# DM1095_Connector.net
KiCad netlist of a schematic drawn in Altium Designer
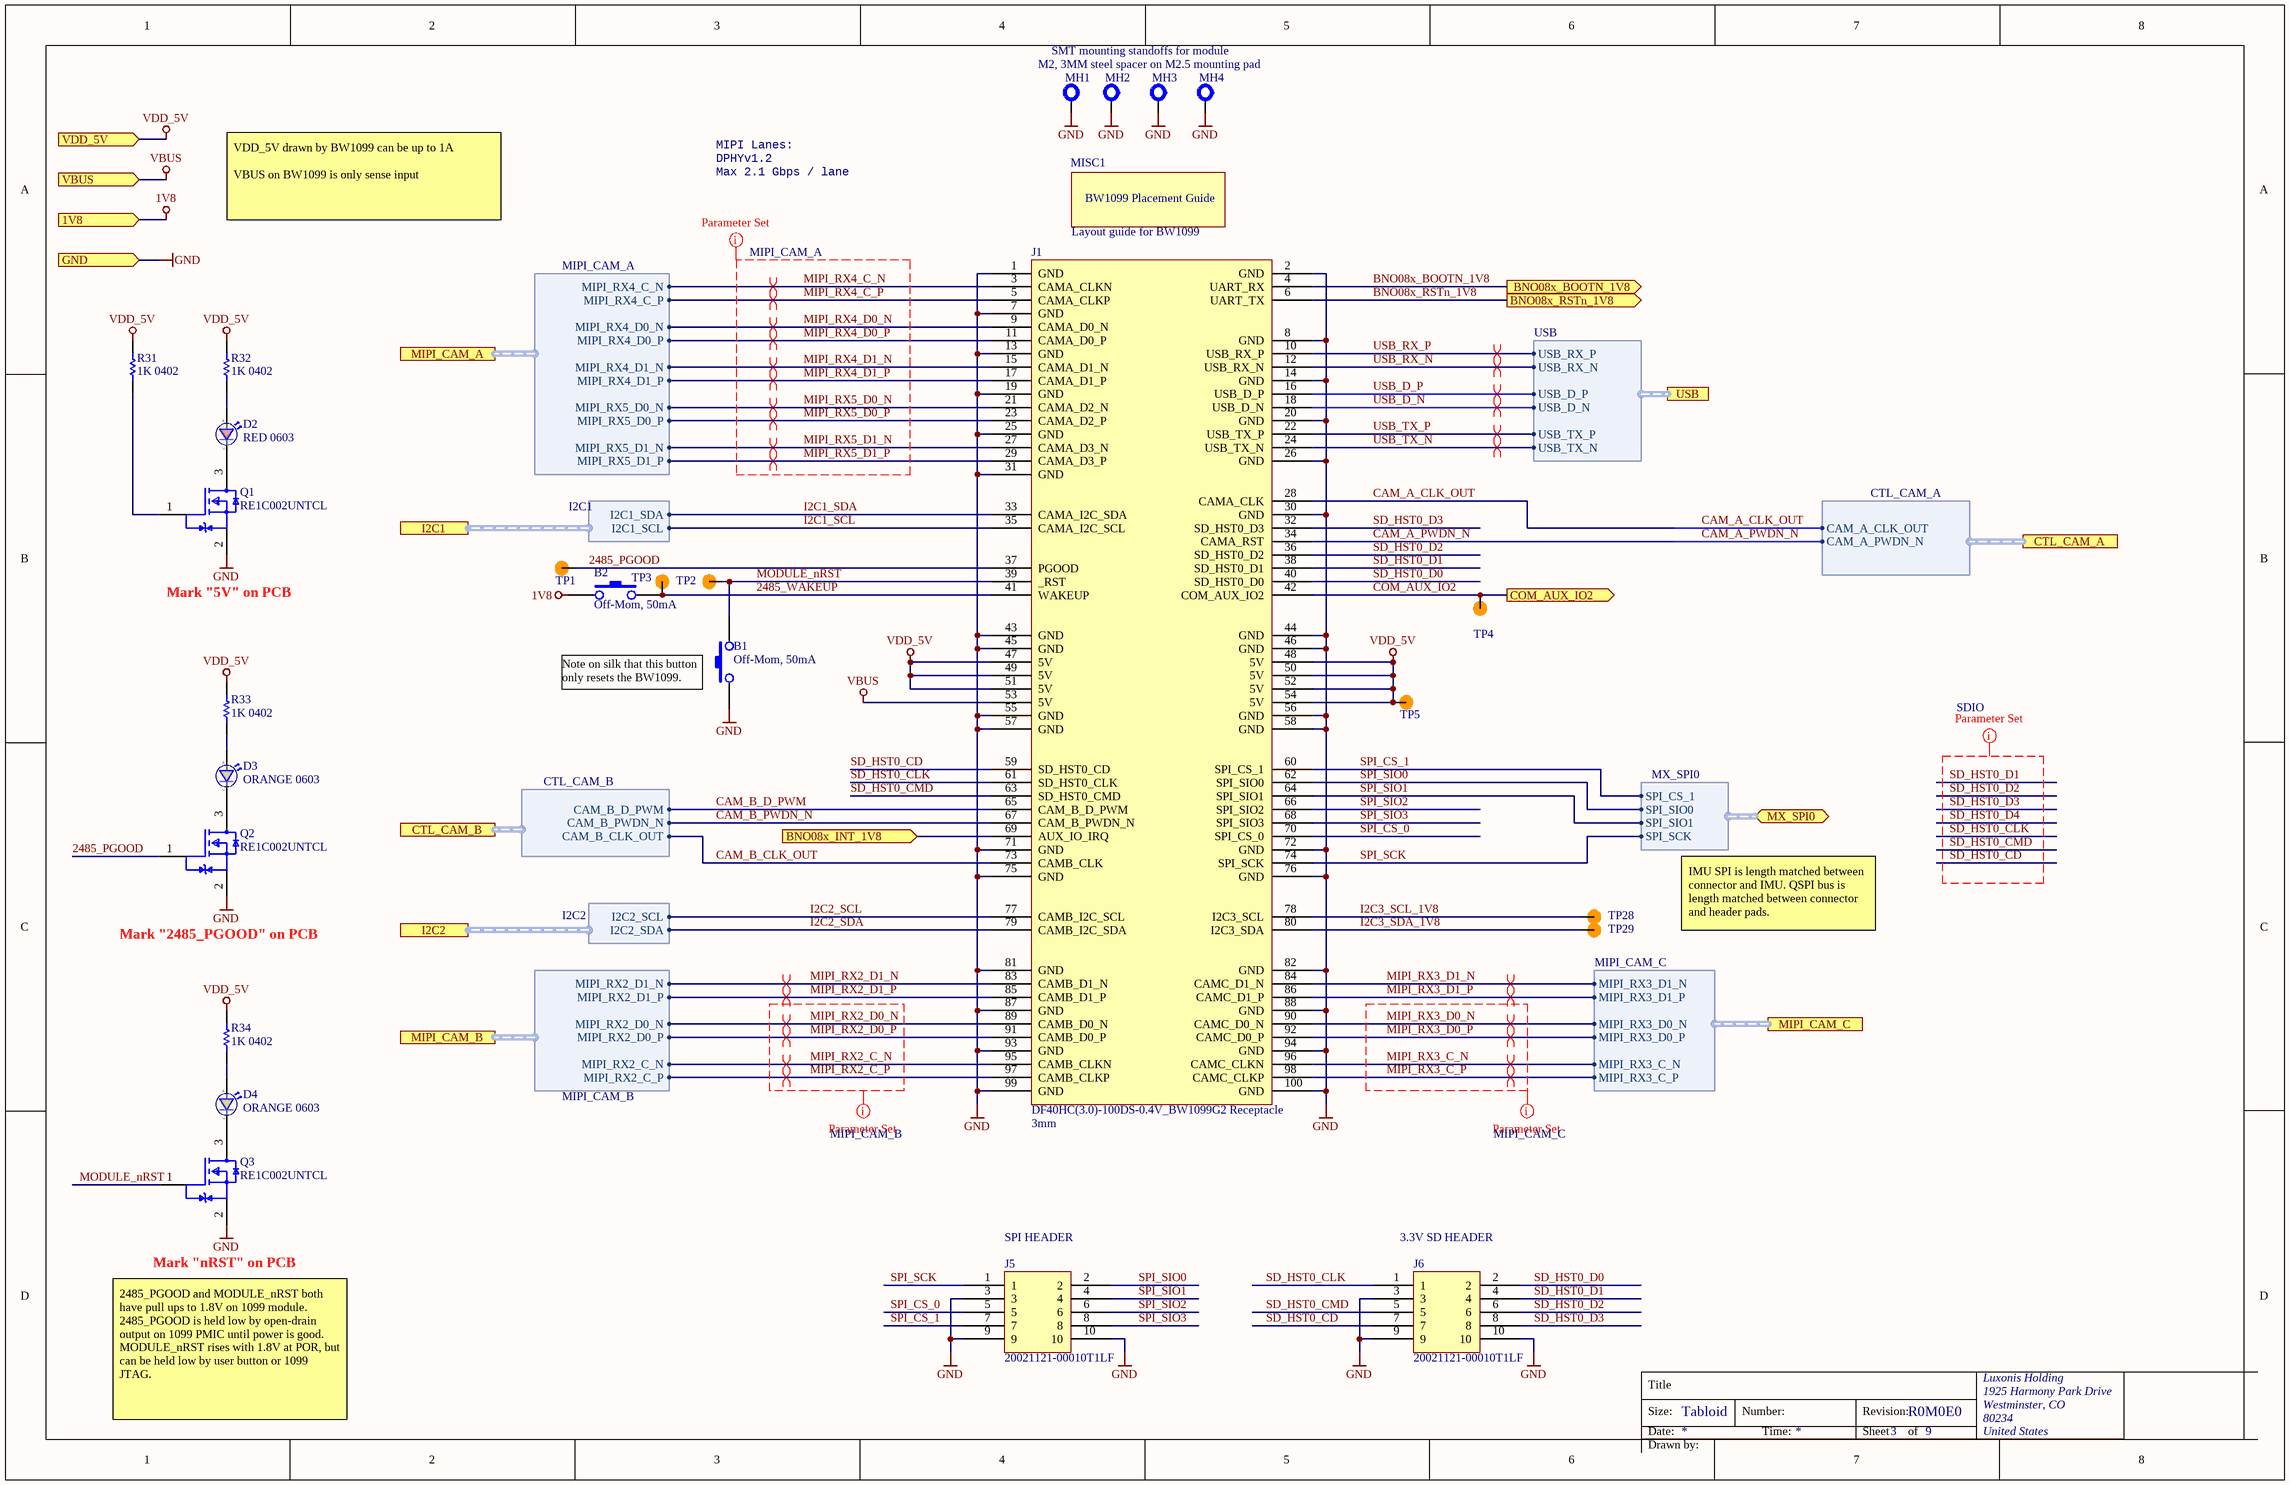
[diagram p0: DM1095_Connector.SchDoc]

(export (version "E")
  (design (tool "Eeschema 10.0.6"))
  (components
    (comp (ref "B1")
      (value "Off-Mom, 50mA")
      (footprint "LuxonisMaster:DTSM-32N-V")
      (description "SWITCH TACTILE SMT 3.5mm * 6mm , brown 160gf")
      (libsource (lib "LuxonisMaster") (part "DTSM-32N-V"))
    )
    (comp (ref "B2")
      (value "Off-Mom, 50mA")
      (footprint "LuxonisMaster:DTSM-32N-V")
      (description "SWITCH TACTILE SMT 3.5mm * 6mm , brown 160gf")
      (libsource (lib "LuxonisMaster") (part "DTSM-32N-V"))
    )
    (comp (ref "D2")
      (value "RED 0603")
      (footprint "LuxonisMaster:SML_D1xx8W")
      (description "LED RED DIFFUSED 0603 SMD Red 620nm LED Indication - Discrete 2.2V 0603 (1608 Metric)")
      (libsource (lib "LuxonisMaster") (part "SML-D12U8WT86"))
    )
    (comp (ref "D3")
      (value "ORANGE 0603")
      (footprint "LuxonisMaster:SML_D1xx8W")
      (description "LED ORANGE DIFFUSED 0603 SMD Orange 605nm LED Indication - Discrete 2.2V 0603 (1608 Metric)")
      (libsource (lib "LuxonisMaster") (part "SML-D12D8WT86"))
    )
    (comp (ref "D4")
      (value "ORANGE 0603")
      (footprint "LuxonisMaster:SML_D1xx8W")
      (description "LED ORANGE DIFFUSED 0603 SMD Orange 605nm LED Indication - Discrete 2.2V 0603 (1608 Metric)")
      (libsource (lib "LuxonisMaster") (part "SML-D12D8WT86"))
    )
    (comp (ref "J1")
      (value "DF40HC(3.0)-100DS-0.4V_BW1099G2 Receptacle")
      (footprint "LuxonisMaster:DF40HC-3.0-100DS-0.4V_minpad")
      (description "CONN RCPT 100POS 0.4MM SMD GOLD")
      (fields (field (name "MATED STACKING HEIGHT") "3mm"))
      (libsource (lib "LuxonisMaster") (part "DF40HC(3.0)-100DS-0.4V_BW1099_G2"))
    )
    (comp (ref "J5")
      (value "20021121-00010T1LF")
      (footprint "LuxonisMaster:20021121-00010T1LF")
      (description "CONN HEADER SMD 10POS 1.27MM")
      (libsource (lib "LuxonisMaster") (part "20021121-00010T1LF"))
    )
    (comp (ref "J6")
      (value "20021121-00010T1LF")
      (footprint "LuxonisMaster:20021121-00010T1LF")
      (description "CONN HEADER SMD 10POS 1.27MM")
      (libsource (lib "LuxonisMaster") (part "20021121-00010T1LF"))
    )
    (comp (ref "MH1")
      (value "M2, 3MM steel spacer on M2.5 mounting pad")
      (footprint "LuxonisMaster:9774030243R")
      (description "MP ROUND STANDOFF M2X0.4 STEEL 3MM")
      (libsource (lib "LuxonisMaster") (part "9774030243R"))
    )
    (comp (ref "MH2")
      (value "M2, 3MM steel spacer on M2.5 mounting pad")
      (footprint "LuxonisMaster:9774030243R")
      (description "MP ROUND STANDOFF M2X0.4 STEEL 3MM")
      (libsource (lib "LuxonisMaster") (part "9774030243R"))
    )
    (comp (ref "MH3")
      (value "M2, 3MM steel spacer on M2.5 mounting pad")
      (footprint "LuxonisMaster:9774030243R")
      (description "MP ROUND STANDOFF M2X0.4 STEEL 3MM")
      (libsource (lib "LuxonisMaster") (part "9774030243R"))
    )
    (comp (ref "MH4")
      (value "M2, 3MM steel spacer on M2.5 mounting pad")
      (footprint "LuxonisMaster:9774030243R")
      (description "MP ROUND STANDOFF M2X0.4 STEEL 3MM")
      (libsource (lib "LuxonisMaster") (part "9774030243R"))
    )
    (comp (ref "MISC1")
      (value "Layout guide for BW1099")
      (footprint "BW1099_R3_KTHSNF_Footprint")
      (description "MISC - Use for aligning BW1099 mount")
      (libsource (lib "LuxonisMaster") (part "BW1099_Footprint"))
    )
    (comp (ref "Q1")
      (value "RE1C002UNTCL")
      (footprint "LuxonisMaster:RE1C002UNTCL")
      (description "VISHAY - SI1062X-T1-GE3 - MOSFET Transistor, N Channel, 530 mA, 20 V, 0.35 ohm, 4.5 V, 1 V")
      (libsource (lib "LuxonisMaster") (part "RE1C002UNTCL"))
    )
    (comp (ref "Q2")
      (value "RE1C002UNTCL")
      (footprint "LuxonisMaster:RE1C002UNTCL")
      (description "VISHAY - SI1062X-T1-GE3 - MOSFET Transistor, N Channel, 530 mA, 20 V, 0.35 ohm, 4.5 V, 1 V")
      (libsource (lib "LuxonisMaster") (part "RE1C002UNTCL"))
    )
    (comp (ref "Q3")
      (value "RE1C002UNTCL")
      (footprint "LuxonisMaster:RE1C002UNTCL")
      (description "VISHAY - SI1062X-T1-GE3 - MOSFET Transistor, N Channel, 530 mA, 20 V, 0.35 ohm, 4.5 V, 1 V")
      (libsource (lib "LuxonisMaster") (part "RE1C002UNTCL"))
    )
    (comp (ref "R31")
      (value "1K 0402")
      (footprint "RES_Altium_Vault_Generic:RESC0402(1005)_L")
      (fields (field (name "TOLERANCE") "1%"))
      (libsource (lib "LuxonisMaster") (part "RC0402FR-071KL"))
    )
    (comp (ref "R32")
      (value "1K 0402")
      (footprint "RES_Altium_Vault_Generic:RESC0402(1005)_L")
      (fields (field (name "TOLERANCE") "1%"))
      (libsource (lib "LuxonisMaster") (part "RC0402FR-071KL"))
    )
    (comp (ref "R33")
      (value "1K 0402")
      (footprint "RES_Altium_Vault_Generic:RESC0402(1005)_L")
      (fields (field (name "TOLERANCE") "1%"))
      (libsource (lib "LuxonisMaster") (part "RC0402FR-071KL"))
    )
    (comp (ref "R34")
      (value "1K 0402")
      (footprint "RES_Altium_Vault_Generic:RESC0402(1005)_L")
      (fields (field (name "TOLERANCE") "1%"))
      (libsource (lib "LuxonisMaster") (part "RC0402FR-071KL"))
    )
    (comp (ref "TP1")
      (value "TP100_200_NS")
      (footprint "LuxonisMaster:TP100_200_NS")
      (libsource (lib "LuxonisMaster") (part "TEST_POINT"))
    )
    (comp (ref "TP2")
      (value "TP100_200_NS")
      (footprint "LuxonisMaster:TP100_200_NS")
      (libsource (lib "LuxonisMaster") (part "TEST_POINT"))
    )
    (comp (ref "TP3")
      (value "TP100_200_NS")
      (footprint "LuxonisMaster:TP100_200_NS")
      (libsource (lib "LuxonisMaster") (part "TEST_POINT"))
    )
    (comp (ref "TP4")
      (value "TP100_200_NS")
      (footprint "LuxonisMaster:TP100_200_NS")
      (libsource (lib "LuxonisMaster") (part "TEST_POINT"))
    )
    (comp (ref "TP5")
      (value "TP100_200_NS")
      (footprint "LuxonisMaster:TP100_200_NS")
      (libsource (lib "LuxonisMaster") (part "TEST_POINT"))
    )
    (comp (ref "TP28")
      (value "TP100_200_NS")
      (footprint "LuxonisMaster:TP100_200_NS")
      (libsource (lib "LuxonisMaster") (part "TEST_POINT"))
    )
    (comp (ref "TP29")
      (value "TP100_200_NS")
      (footprint "LuxonisMaster:TP100_200_NS")
      (libsource (lib "LuxonisMaster") (part "TEST_POINT"))
    )
  )
  (nets
    (net (code "10") (name "/2485_PGOOD") (class "Default")
      (node (ref "J1") (pin "37") (pinfunction "PGOOD_37") (pintype "passive"))
      (node (ref "Q2") (pin "1") (pinfunction "Gate_1") (pintype "passive"))
      (node (ref "TP1") (pin "1") (pintype "passive"))
    )
    (net (code "11") (name "/2485_WAKEUP") (class "Default")
      (node (ref "B2") (pin "2") (pinfunction "2_2") (pintype "passive"))
      (node (ref "J1") (pin "41") (pinfunction "WAKEUP_41") (pintype "passive"))
      (node (ref "TP3") (pin "1") (pintype "passive"))
    )
    (net (code "12") (name "/BNO08x_BOOTN_1V8") (class "Default")
      (node (ref "J1") (pin "4") (pinfunction "UART_RX_4") (pintype "passive"))
    )
    (net (code "13") (name "/BNO08x_INT_1V8") (class "Default")
      (node (ref "J1") (pin "69") (pinfunction "AUX_IO_IRQ_69") (pintype "passive"))
    )
    (net (code "14") (name "/BNO08x_RSTn_1V8") (class "Default")
      (node (ref "J1") (pin "6") (pinfunction "UART_TX_6") (pintype "passive"))
    )
    (net (code "15") (name "/CAM_A_CLK_OUT") (class "Default")
      (node (ref "J1") (pin "28") (pinfunction "CAMA_CLK_28") (pintype "passive"))
    )
    (net (code "16") (name "/CAM_A_PWDN_N") (class "Default")
      (node (ref "J1") (pin "34") (pinfunction "CAMA_RST_34") (pintype "passive"))
    )
    (net (code "17") (name "/CAM_B_CLK_OUT") (class "Default")
      (node (ref "J1") (pin "73") (pinfunction "CAMB_CLK_73") (pintype "passive"))
    )
    (net (code "18") (name "/CAM_B_D_PWM") (class "Default")
      (node (ref "J1") (pin "65") (pinfunction "CAM_B_D_PWM_65") (pintype "passive"))
    )
    (net (code "19") (name "/CAM_B_PWDN_N") (class "Default")
      (node (ref "J1") (pin "67") (pinfunction "CAM_B_PWDN_N_67") (pintype "passive"))
    )
    (net (code "20") (name "/COM_AUX_IO2") (class "Default")
      (node (ref "J1") (pin "42") (pinfunction "COM_AUX_IO2_42") (pintype "passive"))
      (node (ref "TP4") (pin "1") (pintype "passive"))
    )
    (net (code "21") (name "/I2C1_SCL") (class "Default")
      (node (ref "J1") (pin "35") (pinfunction "CAMA_I2C_SCL_35") (pintype "passive"))
    )
    (net (code "22") (name "/I2C1_SDA") (class "Default")
      (node (ref "J1") (pin "33") (pinfunction "CAMA_I2C_SDA_33") (pintype "passive"))
    )
    (net (code "23") (name "/I2C2_SCL") (class "Default")
      (node (ref "J1") (pin "77") (pinfunction "CAMB_I2C_SCL_77") (pintype "passive"))
    )
    (net (code "24") (name "/I2C2_SDA") (class "Default")
      (node (ref "J1") (pin "79") (pinfunction "CAMB_I2C_SDA_79") (pintype "passive"))
    )
    (net (code "25") (name "/I2C3_SCL_1V8") (class "Default")
      (node (ref "J1") (pin "78") (pinfunction "I2C3_SCL_78") (pintype "passive"))
      (node (ref "TP28") (pin "1") (pintype "passive"))
    )
    (net (code "26") (name "/I2C3_SDA_1V8") (class "Default")
      (node (ref "J1") (pin "80") (pinfunction "I2C3_SDA_80") (pintype "passive"))
      (node (ref "TP29") (pin "1") (pintype "passive"))
    )
    (net (code "27") (name "/MIPI_RX2_C_N") (class "Default")
      (node (ref "J1") (pin "95") (pinfunction "CAMB_CLKN_95") (pintype "passive"))
    )
    (net (code "28") (name "/MIPI_RX2_C_P") (class "Default")
      (node (ref "J1") (pin "97") (pinfunction "CAMB_CLKP_97") (pintype "passive"))
    )
    (net (code "29") (name "/MIPI_RX2_D0_N") (class "Default")
      (node (ref "J1") (pin "89") (pinfunction "CAMB_D0_N_89") (pintype "passive"))
    )
    (net (code "30") (name "/MIPI_RX2_D0_P") (class "Default")
      (node (ref "J1") (pin "91") (pinfunction "CAMB_D0_P_91") (pintype "passive"))
    )
    (net (code "31") (name "/MIPI_RX2_D1_N") (class "Default")
      (node (ref "J1") (pin "83") (pinfunction "CAMB_D1_N_83") (pintype "passive"))
    )
    (net (code "32") (name "/MIPI_RX2_D1_P") (class "Default")
      (node (ref "J1") (pin "85") (pinfunction "CAMB_D1_P_85") (pintype "passive"))
    )
    (net (code "33") (name "/MIPI_RX3_C_N") (class "Default")
      (node (ref "J1") (pin "96") (pinfunction "CAMC_CLKN_96") (pintype "passive"))
    )
    (net (code "34") (name "/MIPI_RX3_C_P") (class "Default")
      (node (ref "J1") (pin "98") (pinfunction "CAMC_CLKP_98") (pintype "passive"))
    )
    (net (code "35") (name "/MIPI_RX3_D0_N") (class "Default")
      (node (ref "J1") (pin "90") (pinfunction "CAMC_D0_N_90") (pintype "passive"))
    )
    (net (code "36") (name "/MIPI_RX3_D0_P") (class "Default")
      (node (ref "J1") (pin "92") (pinfunction "CAMC_D0_P_92") (pintype "passive"))
    )
    (net (code "37") (name "/MIPI_RX3_D1_N") (class "Default")
      (node (ref "J1") (pin "84") (pinfunction "CAMC_D1_N_84") (pintype "passive"))
    )
    (net (code "38") (name "/MIPI_RX3_D1_P") (class "Default")
      (node (ref "J1") (pin "86") (pinfunction "CAMC_D1_P_86") (pintype "passive"))
    )
    (net (code "39") (name "/MIPI_RX4_C_N") (class "Default")
      (node (ref "J1") (pin "3") (pinfunction "CAMA_CLKN_3") (pintype "passive"))
    )
    (net (code "40") (name "/MIPI_RX4_C_P") (class "Default")
      (node (ref "J1") (pin "5") (pinfunction "CAMA_CLKP_5") (pintype "passive"))
    )
    (net (code "41") (name "/MIPI_RX4_D0_N") (class "Default")
      (node (ref "J1") (pin "9") (pinfunction "CAMA_D0_N_9") (pintype "passive"))
    )
    (net (code "42") (name "/MIPI_RX4_D0_P") (class "Default")
      (node (ref "J1") (pin "11") (pinfunction "CAMA_D0_P_11") (pintype "passive"))
    )
    (net (code "43") (name "/MIPI_RX4_D1_N") (class "Default")
      (node (ref "J1") (pin "15") (pinfunction "CAMA_D1_N_15") (pintype "passive"))
    )
    (net (code "44") (name "/MIPI_RX4_D1_P") (class "Default")
      (node (ref "J1") (pin "17") (pinfunction "CAMA_D1_P_17") (pintype "passive"))
    )
    (net (code "45") (name "/MIPI_RX5_D0_N") (class "Default")
      (node (ref "J1") (pin "21") (pinfunction "CAMA_D2_N_21") (pintype "passive"))
    )
    (net (code "46") (name "/MIPI_RX5_D0_P") (class "Default")
      (node (ref "J1") (pin "23") (pinfunction "CAMA_D2_P_23") (pintype "passive"))
    )
    (net (code "47") (name "/MIPI_RX5_D1_N") (class "Default")
      (node (ref "J1") (pin "27") (pinfunction "CAMA_D3_N_27") (pintype "passive"))
    )
    (net (code "48") (name "/MIPI_RX5_D1_P") (class "Default")
      (node (ref "J1") (pin "29") (pinfunction "CAMA_D3_P_29") (pintype "passive"))
    )
    (net (code "49") (name "/MODULE_nRST") (class "Default")
      (node (ref "B1") (pin "2") (pinfunction "2_2") (pintype "passive"))
      (node (ref "J1") (pin "39") (pinfunction "_RST_39") (pintype "passive"))
      (node (ref "Q3") (pin "1") (pinfunction "Gate_1") (pintype "passive"))
      (node (ref "TP2") (pin "1") (pintype "passive"))
    )
    (net (code "50") (name "/SD_HST0_CD") (class "Default")
      (node (ref "J1") (pin "59") (pinfunction "SD_HST0_CD_59") (pintype "passive"))
      (node (ref "J6") (pin "7") (pinfunction "7_7") (pintype "passive"))
    )
    (net (code "51") (name "/SD_HST0_CLK") (class "Default")
      (node (ref "J1") (pin "61") (pinfunction "SD_HST0_CLK_61") (pintype "passive"))
      (node (ref "J6") (pin "1") (pinfunction "1_1") (pintype "passive"))
    )
    (net (code "52") (name "/SD_HST0_CMD") (class "Default")
      (node (ref "J1") (pin "63") (pinfunction "SD_HST0_CMD_63") (pintype "passive"))
      (node (ref "J6") (pin "5") (pinfunction "5_5") (pintype "passive"))
    )
    (net (code "53") (name "/SD_HST0_D0") (class "Default")
      (node (ref "J1") (pin "40") (pinfunction "SD_HST0_D0_40") (pintype "passive"))
      (node (ref "J6") (pin "2") (pinfunction "2_2") (pintype "passive"))
    )
    (net (code "54") (name "/SD_HST0_D1") (class "Default")
      (node (ref "J1") (pin "38") (pinfunction "SD_HST0_D1_38") (pintype "passive"))
      (node (ref "J6") (pin "4") (pinfunction "4_4") (pintype "passive"))
    )
    (net (code "55") (name "/SD_HST0_D2") (class "Default")
      (node (ref "J1") (pin "36") (pinfunction "SD_HST0_D2_36") (pintype "passive"))
      (node (ref "J6") (pin "6") (pinfunction "6_6") (pintype "passive"))
    )
    (net (code "56") (name "/SD_HST0_D3") (class "Default")
      (node (ref "J1") (pin "32") (pinfunction "SD_HST0_D3_32") (pintype "passive"))
      (node (ref "J6") (pin "8") (pinfunction "8_8") (pintype "passive"))
    )
    (net (code "58") (name "/SPI_CS_0") (class "Default")
      (node (ref "J1") (pin "70") (pinfunction "SPI_CS_0_70") (pintype "passive"))
      (node (ref "J5") (pin "5") (pinfunction "5_5") (pintype "passive"))
    )
    (net (code "59") (name "/SPI_CS_1") (class "Default")
      (node (ref "J1") (pin "60") (pinfunction "SPI_CS_1_60") (pintype "passive"))
      (node (ref "J5") (pin "7") (pinfunction "7_7") (pintype "passive"))
    )
    (net (code "60") (name "/SPI_SCK") (class "Default")
      (node (ref "J1") (pin "74") (pinfunction "SPI_SCK_74") (pintype "passive"))
      (node (ref "J5") (pin "1") (pinfunction "1_1") (pintype "passive"))
    )
    (net (code "61") (name "/SPI_SIO0") (class "Default")
      (node (ref "J1") (pin "62") (pinfunction "SPI_SIO0_62") (pintype "passive"))
      (node (ref "J5") (pin "2") (pinfunction "2_2") (pintype "passive"))
    )
    (net (code "62") (name "/SPI_SIO1") (class "Default")
      (node (ref "J1") (pin "64") (pinfunction "SPI_SIO1_64") (pintype "passive"))
      (node (ref "J5") (pin "4") (pinfunction "4_4") (pintype "passive"))
    )
    (net (code "63") (name "/SPI_SIO2") (class "Default")
      (node (ref "J1") (pin "66") (pinfunction "SPI_SIO2_66") (pintype "passive"))
      (node (ref "J5") (pin "6") (pinfunction "6_6") (pintype "passive"))
    )
    (net (code "64") (name "/SPI_SIO3") (class "Default")
      (node (ref "J1") (pin "68") (pinfunction "SPI_SIO3_68") (pintype "passive"))
      (node (ref "J5") (pin "8") (pinfunction "8_8") (pintype "passive"))
    )
    (net (code "65") (name "/USB_D_N") (class "Default")
      (node (ref "J1") (pin "18") (pinfunction "USB_D_N_18") (pintype "passive"))
    )
    (net (code "66") (name "/USB_D_P") (class "Default")
      (node (ref "J1") (pin "16") (pinfunction "USB_D_P_16") (pintype "passive"))
    )
    (net (code "67") (name "/USB_RX_N") (class "Default")
      (node (ref "J1") (pin "12") (pinfunction "USB_RX_N_12") (pintype "passive"))
    )
    (net (code "68") (name "/USB_RX_P") (class "Default")
      (node (ref "J1") (pin "10") (pinfunction "USB_RX_P_10") (pintype "passive"))
    )
    (net (code "69") (name "/USB_TX_N") (class "Default")
      (node (ref "J1") (pin "24") (pinfunction "USB_TX_N_24") (pintype "passive"))
    )
    (net (code "70") (name "/USB_TX_P") (class "Default")
      (node (ref "J1") (pin "22") (pinfunction "USB_TX_P_22") (pintype "passive"))
    )
    (net (code "80") (name "1V8") (class "Default")
      (node (ref "B2") (pin "1") (pinfunction "1_1") (pintype "passive"))
    )
    (net (code "81") (name "GND") (class "Default")
      (node (ref "B1") (pin "1") (pinfunction "1_1") (pintype "passive"))
      (node (ref "J1") (pin "1") (pinfunction "GND_1") (pintype "passive"))
      (node (ref "J1") (pin "100") (pinfunction "GND_100") (pintype "passive"))
      (node (ref "J1") (pin "13") (pinfunction "GND_13") (pintype "passive"))
      (node (ref "J1") (pin "14") (pinfunction "GND_14") (pintype "passive"))
      (node (ref "J1") (pin "19") (pinfunction "GND_19") (pintype "passive"))
      (node (ref "J1") (pin "2") (pinfunction "GND_2") (pintype "passive"))
      (node (ref "J1") (pin "20") (pinfunction "GND_20") (pintype "passive"))
      (node (ref "J1") (pin "25") (pinfunction "GND_25") (pintype "passive"))
      (node (ref "J1") (pin "26") (pinfunction "GND_26") (pintype "passive"))
      (node (ref "J1") (pin "30") (pinfunction "GND_30") (pintype "passive"))
      (node (ref "J1") (pin "31") (pinfunction "GND_31") (pintype "passive"))
      (node (ref "J1") (pin "43") (pinfunction "GND_43") (pintype "passive"))
      (node (ref "J1") (pin "44") (pinfunction "GND_44") (pintype "passive"))
      (node (ref "J1") (pin "45") (pinfunction "GND_45") (pintype "passive"))
      (node (ref "J1") (pin "46") (pinfunction "GND_46") (pintype "passive"))
      (node (ref "J1") (pin "55") (pinfunction "GND_55") (pintype "passive"))
      (node (ref "J1") (pin "56") (pinfunction "GND_56") (pintype "passive"))
      (node (ref "J1") (pin "57") (pinfunction "GND_57") (pintype "passive"))
      (node (ref "J1") (pin "58") (pinfunction "GND_58") (pintype "passive"))
      (node (ref "J1") (pin "7") (pinfunction "GND_7") (pintype "passive"))
      (node (ref "J1") (pin "71") (pinfunction "GND_71") (pintype "passive"))
      (node (ref "J1") (pin "72") (pinfunction "GND_72") (pintype "passive"))
      (node (ref "J1") (pin "75") (pinfunction "GND_75") (pintype "passive"))
      (node (ref "J1") (pin "76") (pinfunction "GND_76") (pintype "passive"))
      (node (ref "J1") (pin "8") (pinfunction "GND_8") (pintype "passive"))
      (node (ref "J1") (pin "81") (pinfunction "GND_81") (pintype "passive"))
      (node (ref "J1") (pin "82") (pinfunction "GND_82") (pintype "passive"))
      (node (ref "J1") (pin "87") (pinfunction "GND_87") (pintype "passive"))
      (node (ref "J1") (pin "88") (pinfunction "GND_88") (pintype "passive"))
      (node (ref "J1") (pin "93") (pinfunction "GND_93") (pintype "passive"))
      (node (ref "J1") (pin "94") (pinfunction "GND_94") (pintype "passive"))
      (node (ref "J1") (pin "99") (pinfunction "GND_99") (pintype "passive"))
      (node (ref "J5") (pin "10") (pinfunction "10_10") (pintype "passive"))
      (node (ref "J5") (pin "3") (pinfunction "3_3") (pintype "passive"))
      (node (ref "J5") (pin "9") (pinfunction "9_9") (pintype "passive"))
      (node (ref "J6") (pin "10") (pinfunction "10_10") (pintype "passive"))
      (node (ref "J6") (pin "3") (pinfunction "3_3") (pintype "passive"))
      (node (ref "J6") (pin "9") (pinfunction "9_9") (pintype "passive"))
      (node (ref "MH1") (pin "1") (pintype "passive"))
      (node (ref "MH2") (pin "1") (pintype "passive"))
      (node (ref "MH3") (pin "1") (pintype "passive"))
      (node (ref "MH4") (pin "1") (pintype "passive"))
      (node (ref "Q1") (pin "2") (pinfunction "Source_2") (pintype "passive"))
      (node (ref "Q2") (pin "2") (pinfunction "Source_2") (pintype "passive"))
      (node (ref "Q3") (pin "2") (pinfunction "Source_2") (pintype "passive"))
    )
    (net (code "82") (name "Net-(D2-A)") (class "Default")
      (node (ref "D2") (pin "2") (pinfunction "A_2") (pintype "passive"))
      (node (ref "R32") (pin "1") (pinfunction "1_1") (pintype "passive"))
    )
    (net (code "83") (name "Net-(D2-C)") (class "Default")
      (node (ref "D2") (pin "1") (pinfunction "C_1") (pintype "passive"))
      (node (ref "Q1") (pin "3") (pinfunction "Drain_3") (pintype "passive"))
    )
    (net (code "84") (name "Net-(D3-A)") (class "Default")
      (node (ref "D3") (pin "2") (pinfunction "A_2") (pintype "passive"))
      (node (ref "R33") (pin "1") (pinfunction "1_1") (pintype "passive"))
    )
    (net (code "85") (name "Net-(D3-C)") (class "Default")
      (node (ref "D3") (pin "1") (pinfunction "C_1") (pintype "passive"))
      (node (ref "Q2") (pin "3") (pinfunction "Drain_3") (pintype "passive"))
    )
    (net (code "86") (name "Net-(D4-A)") (class "Default")
      (node (ref "D4") (pin "2") (pinfunction "A_2") (pintype "passive"))
      (node (ref "R34") (pin "1") (pinfunction "1_1") (pintype "passive"))
    )
    (net (code "87") (name "Net-(D4-C)") (class "Default")
      (node (ref "D4") (pin "1") (pinfunction "C_1") (pintype "passive"))
      (node (ref "Q3") (pin "3") (pinfunction "Drain_3") (pintype "passive"))
    )
    (net (code "88") (name "Net-(Q1-Gate)") (class "Default")
      (node (ref "Q1") (pin "1") (pinfunction "Gate_1") (pintype "passive"))
      (node (ref "R31") (pin "1") (pinfunction "1_1") (pintype "passive"))
    )
    (net (code "89") (name "VBUS") (class "Default")
      (node (ref "J1") (pin "53") (pinfunction "5V_53") (pintype "passive"))
    )
    (net (code "90") (name "VDD_5V") (class "Default")
      (node (ref "J1") (pin "47") (pinfunction "5V_47") (pintype "passive"))
      (node (ref "J1") (pin "48") (pinfunction "5V_48") (pintype "passive"))
      (node (ref "J1") (pin "49") (pinfunction "5V_49") (pintype "passive"))
      (node (ref "J1") (pin "50") (pinfunction "5V_50") (pintype "passive"))
      (node (ref "J1") (pin "51") (pinfunction "5V_51") (pintype "passive"))
      (node (ref "J1") (pin "52") (pinfunction "5V_52") (pintype "passive"))
      (node (ref "J1") (pin "54") (pinfunction "5V_54") (pintype "passive"))
      (node (ref "R31") (pin "2") (pinfunction "2_2") (pintype "passive"))
      (node (ref "R32") (pin "2") (pinfunction "2_2") (pintype "passive"))
      (node (ref "R33") (pin "2") (pinfunction "2_2") (pintype "passive"))
      (node (ref "R34") (pin "2") (pinfunction "2_2") (pintype "passive"))
      (node (ref "TP5") (pin "1") (pintype "passive"))
    )
  )
)
